# programmer.net
KiCad netlist of a schematic drawn in EAGLE
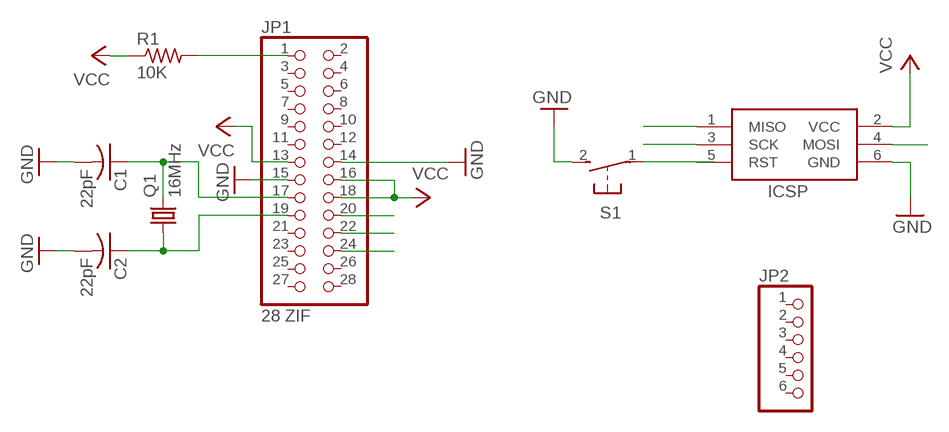
[diagram p0: schematic, sheet 1]

(export (version "E")
  (design (tool "Eeschema 10.0.6"))
  (components
    (comp (ref "C1")
      (value "22pF")
      (footprint "eagle-import:C025-025X050")
      (libsource (lib "eagle-import") (part "C-US025-025X050"))
    )
    (comp (ref "C2")
      (value "22pF")
      (footprint "eagle-import:C025-025X050")
      (libsource (lib "eagle-import") (part "C-US025-025X050"))
    )
    (comp (ref "ICSP")
      (value "AVRISP-6")
      (footprint "eagle-import:AVRISP")
      (libsource (lib "eagle-import") (part "AVRISP-6"))
    )
    (comp (ref "JP1")
      (value "28 ZIF")
      (footprint "eagle-import:2X14")
      (libsource (lib "eagle-import") (part "PINHD-2X14"))
    )
    (comp (ref "JP2")
      (value "PINHD-1X6")
      (footprint "eagle-import:1X06")
      (libsource (lib "eagle-import") (part "PINHD-1X6"))
    )
    (comp (ref "Q1")
      (value "16MHz")
      (footprint "eagle-import:HC49_S")
      (libsource (lib "eagle-import") (part "CRYSTALHC49S"))
    )
    (comp (ref "R1")
      (value "10K")
      (footprint "eagle-import:0207_10")
      (libsource (lib "eagle-import") (part "R-US_0207/10"))
    )
    (comp (ref "S1")
      (value "31-XX")
      (footprint "eagle-import:B3F-31XX")
      (libsource (lib "eagle-import") (part "31-XX"))
    )
  )
  (nets
    (net (code "1") (name "/MISO") (class "Default")
      (node (ref "ICSP") (pin "1") (pinfunction "MISO_1") (pintype "input"))
      (node (ref "JP1") (pin "22") (pinfunction "22_22") (pintype "passive"))
    )
    (net (code "2") (name "/MOSI") (class "Default")
      (node (ref "ICSP") (pin "4") (pinfunction "MOSI_4") (pintype "output"))
      (node (ref "JP1") (pin "24") (pinfunction "24_24") (pintype "passive"))
    )
    (net (code "3") (name "/RESET") (class "Default")
      (node (ref "JP1") (pin "1") (pinfunction "1_1") (pintype "passive"))
      (node (ref "R1") (pin "2") (pinfunction "2_2") (pintype "passive"))
      (node (ref "S1") (pin "1") (pinfunction "P_1") (pintype "passive"))
    )
    (net (code "4") (name "/SCK") (class "Default")
      (node (ref "ICSP") (pin "3") (pinfunction "SCK_3") (pintype "output"))
      (node (ref "JP1") (pin "20") (pinfunction "20_20") (pintype "passive"))
    )
    (net (code "5") (name "GND") (class "Default")
      (node (ref "C1") (pin "2") (pinfunction "2_2") (pintype "passive"))
      (node (ref "C2") (pin "2") (pinfunction "2_2") (pintype "passive"))
      (node (ref "ICSP") (pin "6") (pinfunction "GND_6") (pintype "power_in"))
      (node (ref "JP1") (pin "14") (pinfunction "14_14") (pintype "passive"))
      (node (ref "JP1") (pin "15") (pinfunction "15_15") (pintype "passive"))
      (node (ref "S1") (pin "2") (pinfunction "S_2") (pintype "passive"))
    )
    (net (code "6") (name "Net-(C1-Pad1)") (class "Default")
      (node (ref "C1") (pin "1") (pinfunction "1_1") (pintype "passive"))
      (node (ref "JP1") (pin "17") (pinfunction "17_17") (pintype "passive"))
      (node (ref "Q1") (pin "2") (pinfunction "2_2") (pintype "passive"))
    )
    (net (code "7") (name "Net-(C2-Pad1)") (class "Default")
      (node (ref "C2") (pin "1") (pinfunction "1_1") (pintype "passive"))
      (node (ref "JP1") (pin "19") (pinfunction "19_19") (pintype "passive"))
      (node (ref "Q1") (pin "1") (pinfunction "1_1") (pintype "passive"))
    )
    (net (code "8") (name "VCC") (class "Default")
      (node (ref "ICSP") (pin "2") (pinfunction "VCC_2") (pintype "power_in"))
      (node (ref "JP1") (pin "13") (pinfunction "13_13") (pintype "passive"))
      (node (ref "JP1") (pin "16") (pinfunction "16_16") (pintype "passive"))
      (node (ref "JP1") (pin "18") (pinfunction "18_18") (pintype "passive"))
      (node (ref "R1") (pin "1") (pinfunction "1_1") (pintype "passive"))
    )
    (net (code "9") (name "unconnected-(ICSP-RST-Pad5)") (class "Default")
      (node (ref "ICSP") (pin "5") (pinfunction "RST_5") (pintype "output"))
    )
    (net (code "10") (name "unconnected-(JP1-Pad2)") (class "Default")
      (node (ref "JP1") (pin "2") (pinfunction "2_2") (pintype "passive"))
    )
    (net (code "11") (name "unconnected-(JP1-Pad3)") (class "Default")
      (node (ref "JP1") (pin "3") (pinfunction "3_3") (pintype "passive"))
    )
    (net (code "12") (name "unconnected-(JP1-Pad4)") (class "Default")
      (node (ref "JP1") (pin "4") (pinfunction "4_4") (pintype "passive"))
    )
    (net (code "13") (name "unconnected-(JP1-Pad5)") (class "Default")
      (node (ref "JP1") (pin "5") (pinfunction "5_5") (pintype "passive"))
    )
    (net (code "14") (name "unconnected-(JP1-Pad6)") (class "Default")
      (node (ref "JP1") (pin "6") (pinfunction "6_6") (pintype "passive"))
    )
    (net (code "15") (name "unconnected-(JP1-Pad7)") (class "Default")
      (node (ref "JP1") (pin "7") (pinfunction "7_7") (pintype "passive"))
    )
    (net (code "16") (name "unconnected-(JP1-Pad8)") (class "Default")
      (node (ref "JP1") (pin "8") (pinfunction "8_8") (pintype "passive"))
    )
    (net (code "17") (name "unconnected-(JP1-Pad9)") (class "Default")
      (node (ref "JP1") (pin "9") (pinfunction "9_9") (pintype "passive"))
    )
    (net (code "18") (name "unconnected-(JP1-Pad10)") (class "Default")
      (node (ref "JP1") (pin "10") (pinfunction "10_10") (pintype "passive"))
    )
    (net (code "19") (name "unconnected-(JP1-Pad11)") (class "Default")
      (node (ref "JP1") (pin "11") (pinfunction "11_11") (pintype "passive"))
    )
    (net (code "20") (name "unconnected-(JP1-Pad12)") (class "Default")
      (node (ref "JP1") (pin "12") (pinfunction "12_12") (pintype "passive"))
    )
    (net (code "21") (name "unconnected-(JP1-Pad21)") (class "Default")
      (node (ref "JP1") (pin "21") (pinfunction "21_21") (pintype "passive"))
    )
    (net (code "22") (name "unconnected-(JP1-Pad23)") (class "Default")
      (node (ref "JP1") (pin "23") (pinfunction "23_23") (pintype "passive"))
    )
    (net (code "23") (name "unconnected-(JP1-Pad25)") (class "Default")
      (node (ref "JP1") (pin "25") (pinfunction "25_25") (pintype "passive"))
    )
    (net (code "24") (name "unconnected-(JP1-Pad26)") (class "Default")
      (node (ref "JP1") (pin "26") (pinfunction "26_26") (pintype "passive"))
    )
    (net (code "25") (name "unconnected-(JP1-Pad27)") (class "Default")
      (node (ref "JP1") (pin "27") (pinfunction "27_27") (pintype "passive"))
    )
    (net (code "26") (name "unconnected-(JP1-Pad28)") (class "Default")
      (node (ref "JP1") (pin "28") (pinfunction "28_28") (pintype "passive"))
    )
    (net (code "27") (name "unconnected-(JP2-Pad1)") (class "Default")
      (node (ref "JP2") (pin "1") (pinfunction "1_1") (pintype "passive"))
    )
    (net (code "28") (name "unconnected-(JP2-Pad2)") (class "Default")
      (node (ref "JP2") (pin "2") (pinfunction "2_2") (pintype "passive"))
    )
    (net (code "29") (name "unconnected-(JP2-Pad3)") (class "Default")
      (node (ref "JP2") (pin "3") (pinfunction "3_3") (pintype "passive"))
    )
    (net (code "30") (name "unconnected-(JP2-Pad4)") (class "Default")
      (node (ref "JP2") (pin "4") (pinfunction "4_4") (pintype "passive"))
    )
    (net (code "31") (name "unconnected-(JP2-Pad5)") (class "Default")
      (node (ref "JP2") (pin "5") (pinfunction "5_5") (pintype "passive"))
    )
    (net (code "32") (name "unconnected-(JP2-Pad6)") (class "Default")
      (node (ref "JP2") (pin "6") (pinfunction "6_6") (pintype "passive"))
    )
  )
)
